# Sensors.net
KiCad netlist of a schematic drawn in Altium Designer
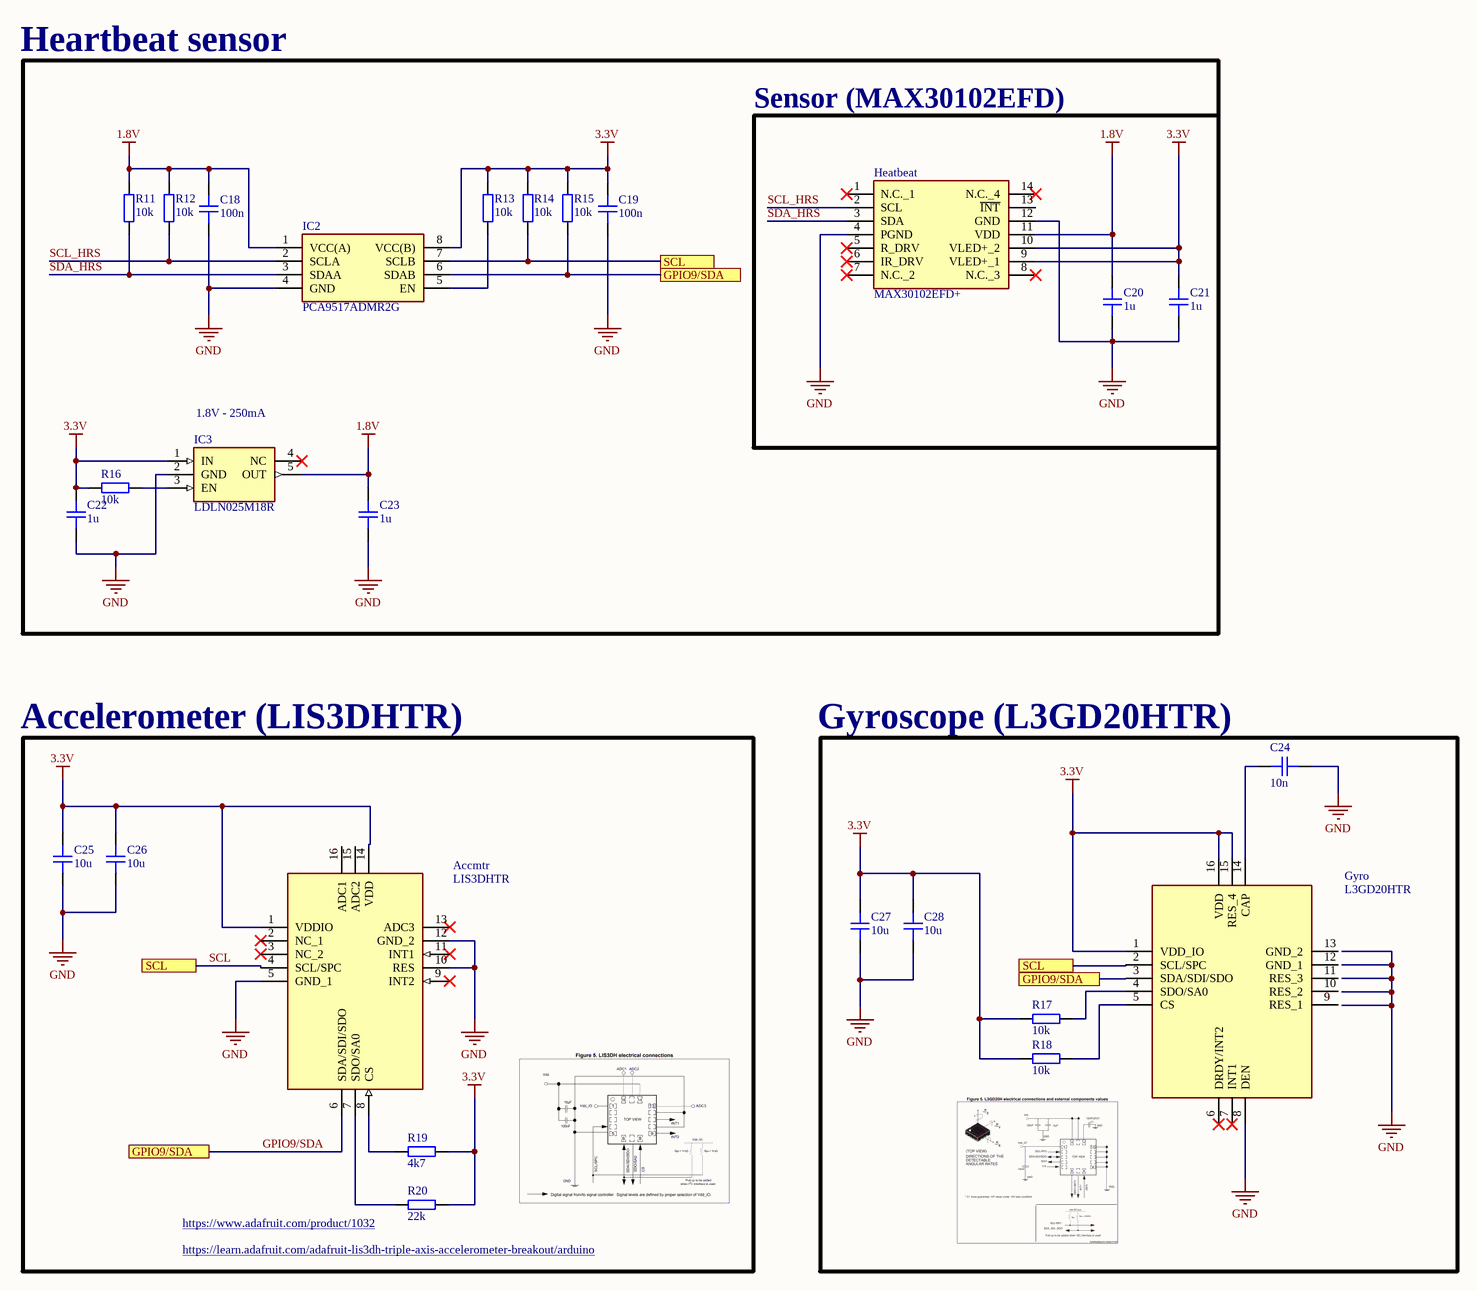
[diagram p0: Sensors.SchDoc]

(export (version "E")
  (design (tool "Eeschema 10.0.6"))
  (components
    (comp (ref "Accmtr")
      (value "LIS3DHTR")
      (footprint "PCB_Lib_DaanHeetkamp:LIS3DHTR")
      (description "Accelerometer")
      (fields (field (name "MOUSER PART NUMBER") "511-LIS3DHTR"))
      (libsource (lib "Schem_Lib_DaanHeetkamp.") (part "LIS3DHTR"))
    )
    (comp (ref "C18")
      (value "100n")
      (footprint "CAP_1206")
      (description "Capacitor SMD 1206 16V")
      (libsource (lib "Schem_Lib_DaanHeetkamp.") (part "CAP_1206_16V"))
    )
    (comp (ref "C19")
      (value "100n")
      (footprint "CAP_1206")
      (description "Capacitor SMD 1206 16V")
      (libsource (lib "Schem_Lib_DaanHeetkamp.") (part "CAP_1206_16V"))
    )
    (comp (ref "C20")
      (value "1u")
      (footprint "CAP_1206")
      (description "Capacitor SMD 1206 16V")
      (libsource (lib "Schem_Lib_DaanHeetkamp.") (part "CAP_1206_16V"))
    )
    (comp (ref "C21")
      (value "1u")
      (footprint "CAP_1206")
      (description "Capacitor SMD 1206 16V")
      (libsource (lib "Schem_Lib_DaanHeetkamp.") (part "CAP_1206_16V"))
    )
    (comp (ref "C22")
      (value "1u")
      (footprint "CAP_1206")
      (description "Capacitor SMD 1206 16V")
      (libsource (lib "Schem_Lib_DaanHeetkamp.") (part "CAP_1206_16V"))
    )
    (comp (ref "C23")
      (value "1u")
      (footprint "CAP_1206")
      (description "Capacitor SMD 1206 16V")
      (libsource (lib "Schem_Lib_DaanHeetkamp.") (part "CAP_1206_16V"))
    )
    (comp (ref "C24")
      (value "10n")
      (footprint "CAP_1206")
      (description "Capacitor SMD 1206 50V")
      (libsource (lib "Schem_Lib_DaanHeetkamp.") (part "CAP_1206_50V"))
    )
    (comp (ref "C25")
      (value "10u")
      (footprint "CAP_1206")
      (description "Capacitor SMD 1206 50V")
      (libsource (lib "Schem_Lib_DaanHeetkamp.") (part "CAP_1206_50V"))
    )
    (comp (ref "C26")
      (value "10u")
      (footprint "CAP_1206")
      (description "Capacitor SMD 1206 50V")
      (libsource (lib "Schem_Lib_DaanHeetkamp.") (part "CAP_1206_50V"))
    )
    (comp (ref "C27")
      (value "10u")
      (footprint "CAP_1206")
      (description "Capacitor SMD 1206 50V")
      (libsource (lib "Schem_Lib_DaanHeetkamp.") (part "CAP_1206_50V"))
    )
    (comp (ref "C28")
      (value "10u")
      (footprint "CAP_1206")
      (description "Capacitor SMD 1206 50V")
      (libsource (lib "Schem_Lib_DaanHeetkamp.") (part "CAP_1206_50V"))
    )
    (comp (ref "Gyro")
      (value "L3GD20HTR")
      (footprint "PCB_Lib_DaanHeetkamp:H3LIS100DLTR")
      (description "MEMS motion sensor:\r\n three-axis digital output gyroscope")
      (fields (field (name "MOUSER PART NUMBER") "511-L3GD20HTR"))
      (libsource (lib "Schem_Lib_DaanHeetkamp.") (part "L3GD20HTR"))
    )
    (comp (ref "Heatbeat")
      (value "MAX30102EFD+")
      (footprint "PCB_Lib_DaanHeetkamp:14-LEAD-OESIP")
      (description "Integrated Circuit")
      (fields (field (name "MOUSER PART NUMBER") "700-MAX30102EFD+"))
      (libsource (lib "Schem_Lib_DaanHeetkamp.") (part "MAX30102EFD+"))
    )
    (comp (ref "IC2")
      (value "PCA9517ADMR2G")
      (footprint "PCB_Lib_DaanHeetkamp:SOP65P490X110-8N")
      (description "Integrated Circuit")
      (fields (field (name "MOUSER PART NUMBER") "863-PCA9517ADMR2G"))
      (libsource (lib "Schem_Lib_DaanHeetkamp.") (part "PCA9517ADMR2G"))
    )
    (comp (ref "IC3")
      (value "LDLN025M18R")
      (footprint "PCB_Lib_DaanHeetkamp:SOT95P280X145-5N")
      (description "Integrated Circuit")
      (fields (field (name "MOUSER PART NUMBER") "511-LDLN025M18R"))
      (libsource (lib "Schem_Lib_DaanHeetkamp.") (part "LDLN025M18R"))
    )
    (comp (ref "R11")
      (value "10k")
      (footprint "RES_1206")
      (description "Resistor SMD 1206")
      (libsource (lib "Schem_Lib_DaanHeetkamp.") (part "RES_1206"))
    )
    (comp (ref "R12")
      (value "10k")
      (footprint "RES_1206")
      (description "Resistor SMD 1206")
      (libsource (lib "Schem_Lib_DaanHeetkamp.") (part "RES_1206"))
    )
    (comp (ref "R13")
      (value "10k")
      (footprint "RES_1206")
      (description "Resistor SMD 1206")
      (libsource (lib "Schem_Lib_DaanHeetkamp.") (part "RES_1206"))
    )
    (comp (ref "R14")
      (value "10k")
      (footprint "RES_1206")
      (description "Resistor SMD 1206")
      (libsource (lib "Schem_Lib_DaanHeetkamp.") (part "RES_1206"))
    )
    (comp (ref "R15")
      (value "10k")
      (footprint "RES_1206")
      (description "Resistor SMD 1206")
      (libsource (lib "Schem_Lib_DaanHeetkamp.") (part "RES_1206"))
    )
    (comp (ref "R16")
      (value "10k")
      (footprint "RES_1206")
      (description "Resistor SMD 1206")
      (libsource (lib "Schem_Lib_DaanHeetkamp.") (part "RES_1206"))
    )
    (comp (ref "R17")
      (value "10k")
      (footprint "RES_1206")
      (description "Resistor SMD 1206")
      (libsource (lib "Schem_Lib_DaanHeetkamp.") (part "RES_1206"))
    )
    (comp (ref "R18")
      (value "10k")
      (footprint "RES_1206")
      (description "Resistor SMD 1206")
      (libsource (lib "Schem_Lib_DaanHeetkamp.") (part "RES_1206"))
    )
    (comp (ref "R19")
      (value "4k7")
      (footprint "RES_1206")
      (description "Resistor SMD 1206")
      (libsource (lib "Schem_Lib_DaanHeetkamp.") (part "RES_1206"))
    )
    (comp (ref "R20")
      (value "22k")
      (footprint "RES_1206")
      (description "Resistor SMD 1206")
      (libsource (lib "Schem_Lib_DaanHeetkamp.") (part "RES_1206"))
    )
  )
  (nets
    (net (code "1") (name "/GPIO9{slash}SDA") (class "Default")
      (node (ref "Accmtr") (pin "6") (pinfunction "SDA/SDI/SDO_6") (pintype "passive"))
      (node (ref "Gyro") (pin "3") (pinfunction "SDA/SDI/SDO_3") (pintype "passive"))
      (node (ref "IC2") (pin "6") (pinfunction "SDAB_6") (pintype "passive"))
      (node (ref "R15") (pin "2") (pinfunction "2_2") (pintype "passive"))
    )
    (net (code "2") (name "/SCL") (class "Default")
      (node (ref "Accmtr") (pin "4") (pinfunction "SCL/SPC_4") (pintype "passive"))
      (node (ref "Gyro") (pin "2") (pinfunction "SCL/SPC_2") (pintype "passive"))
      (node (ref "IC2") (pin "7") (pinfunction "SCLB_7") (pintype "passive"))
      (node (ref "R14") (pin "2") (pinfunction "2_2") (pintype "passive"))
    )
    (net (code "3") (name "/SCL_HRS") (class "Default")
      (node (ref "Heatbeat") (pin "2") (pinfunction "SCL_2") (pintype "passive"))
      (node (ref "IC2") (pin "2") (pinfunction "SCLA_2") (pintype "passive"))
      (node (ref "R12") (pin "2") (pinfunction "2_2") (pintype "passive"))
    )
    (net (code "4") (name "/SDA_HRS") (class "Default")
      (node (ref "Heatbeat") (pin "3") (pinfunction "SDA_3") (pintype "passive"))
      (node (ref "IC2") (pin "3") (pinfunction "SDAA_3") (pintype "passive"))
      (node (ref "R11") (pin "2") (pinfunction "2_2") (pintype "passive"))
    )
    (net (code "5") (name "1.8V") (class "Default")
      (node (ref "C18") (pin "2") (pinfunction "2_2") (pintype "passive"))
      (node (ref "C20") (pin "2") (pinfunction "2_2") (pintype "passive"))
      (node (ref "C23") (pin "2") (pinfunction "2_2") (pintype "passive"))
      (node (ref "Heatbeat") (pin "11") (pinfunction "VDD_11") (pintype "passive"))
      (node (ref "IC2") (pin "1") (pinfunction "VCC(A)_1") (pintype "passive"))
      (node (ref "IC3") (pin "5") (pinfunction "OUT_5") (pintype "output"))
      (node (ref "R11") (pin "1") (pinfunction "1_1") (pintype "passive"))
      (node (ref "R12") (pin "1") (pinfunction "1_1") (pintype "passive"))
    )
    (net (code "6") (name "3.3V") (class "Default")
      (node (ref "Accmtr") (pin "1") (pinfunction "VDDIO_1") (pintype "power_in"))
      (node (ref "Accmtr") (pin "14") (pinfunction "VDD_14") (pintype "power_in"))
      (node (ref "C19") (pin "2") (pinfunction "2_2") (pintype "passive"))
      (node (ref "C21") (pin "2") (pinfunction "2_2") (pintype "passive"))
      (node (ref "C22") (pin "2") (pinfunction "2_2") (pintype "passive"))
      (node (ref "C25") (pin "2") (pinfunction "2_2") (pintype "passive"))
      (node (ref "C26") (pin "2") (pinfunction "2_2") (pintype "passive"))
      (node (ref "C27") (pin "2") (pinfunction "2_2") (pintype "passive"))
      (node (ref "C28") (pin "2") (pinfunction "2_2") (pintype "passive"))
      (node (ref "Gyro") (pin "1") (pinfunction "VDD_IO_1") (pintype "passive"))
      (node (ref "Gyro") (pin "15") (pinfunction "RES_4_15") (pintype "passive"))
      (node (ref "Gyro") (pin "16") (pinfunction "VDD_16") (pintype "passive"))
      (node (ref "Heatbeat") (pin "10") (pinfunction "VLED+_2_10") (pintype "passive"))
      (node (ref "Heatbeat") (pin "9") (pinfunction "VLED+_1_9") (pintype "passive"))
      (node (ref "IC2") (pin "8") (pinfunction "VCC(B)_8") (pintype "passive"))
      (node (ref "IC3") (pin "1") (pinfunction "IN_1") (pintype "input"))
      (node (ref "R13") (pin "1") (pinfunction "1_1") (pintype "passive"))
      (node (ref "R14") (pin "1") (pinfunction "1_1") (pintype "passive"))
      (node (ref "R15") (pin "1") (pinfunction "1_1") (pintype "passive"))
      (node (ref "R16") (pin "1") (pinfunction "1_1") (pintype "passive"))
      (node (ref "R17") (pin "2") (pinfunction "2_2") (pintype "passive"))
      (node (ref "R18") (pin "2") (pinfunction "2_2") (pintype "passive"))
      (node (ref "R19") (pin "1") (pinfunction "1_1") (pintype "passive"))
      (node (ref "R20") (pin "1") (pinfunction "1_1") (pintype "passive"))
    )
    (net (code "7") (name "GND") (class "Default")
      (node (ref "Accmtr") (pin "10") (pinfunction "RES_10") (pintype "passive"))
      (node (ref "Accmtr") (pin "12") (pinfunction "GND_2_12") (pintype "power_in"))
      (node (ref "Accmtr") (pin "5") (pinfunction "GND_1_5") (pintype "power_in"))
      (node (ref "C18") (pin "1") (pinfunction "1_1") (pintype "passive"))
      (node (ref "C19") (pin "1") (pinfunction "1_1") (pintype "passive"))
      (node (ref "C20") (pin "1") (pinfunction "1_1") (pintype "passive"))
      (node (ref "C21") (pin "1") (pinfunction "1_1") (pintype "passive"))
      (node (ref "C22") (pin "1") (pinfunction "1_1") (pintype "passive"))
      (node (ref "C23") (pin "1") (pinfunction "1_1") (pintype "passive"))
      (node (ref "C24") (pin "2") (pinfunction "2_2") (pintype "passive"))
      (node (ref "C25") (pin "1") (pinfunction "1_1") (pintype "passive"))
      (node (ref "C26") (pin "1") (pinfunction "1_1") (pintype "passive"))
      (node (ref "C27") (pin "1") (pinfunction "1_1") (pintype "passive"))
      (node (ref "C28") (pin "1") (pinfunction "1_1") (pintype "passive"))
      (node (ref "Gyro") (pin "8") (pinfunction "DEN_8") (pintype "passive"))
      (node (ref "Heatbeat") (pin "12") (pinfunction "GND_12") (pintype "passive"))
      (node (ref "Heatbeat") (pin "4") (pinfunction "PGND_4") (pintype "passive"))
      (node (ref "IC2") (pin "4") (pinfunction "GND_4") (pintype "passive"))
      (node (ref "IC3") (pin "2") (pinfunction "GND_2") (pintype "power_in"))
    )
    (net (code "8") (name "Net-(Accmtr-CS)") (class "Default")
      (node (ref "Accmtr") (pin "8") (pinfunction "CS_8") (pintype "input"))
      (node (ref "R19") (pin "2") (pinfunction "2_2") (pintype "passive"))
    )
    (net (code "9") (name "Net-(Accmtr-SDO{slash}SA0)") (class "Default")
      (node (ref "Accmtr") (pin "7") (pinfunction "SDO/SA0_7") (pintype "passive"))
      (node (ref "R20") (pin "2") (pinfunction "2_2") (pintype "passive"))
    )
    (net (code "10") (name "Net-(Gyro-CAP)") (class "Default")
      (node (ref "C24") (pin "1") (pinfunction "1_1") (pintype "passive"))
      (node (ref "Gyro") (pin "14") (pinfunction "CAP_14") (pintype "passive"))
    )
    (net (code "11") (name "Net-(Gyro-CS)") (class "Default")
      (node (ref "Gyro") (pin "5") (pinfunction "CS_5") (pintype "passive"))
      (node (ref "R18") (pin "1") (pinfunction "1_1") (pintype "passive"))
    )
    (net (code "12") (name "Net-(Gyro-SDO{slash}SA0)") (class "Default")
      (node (ref "Gyro") (pin "4") (pinfunction "SDO/SA0_4") (pintype "passive"))
      (node (ref "R17") (pin "1") (pinfunction "1_1") (pintype "passive"))
    )
    (net (code "13") (name "Net-(IC2-EN)") (class "Default")
      (node (ref "IC2") (pin "5") (pinfunction "EN_5") (pintype "passive"))
      (node (ref "R13") (pin "2") (pinfunction "2_2") (pintype "passive"))
    )
    (net (code "14") (name "Net-(IC3-EN)") (class "Default")
      (node (ref "IC3") (pin "3") (pinfunction "EN_3") (pintype "input"))
      (node (ref "R16") (pin "2") (pinfunction "2_2") (pintype "passive"))
    )
    (net (code "15") (name "unconnected-(Accmtr-ADC1-Pad16)") (class "Default")
      (node (ref "Accmtr") (pin "16") (pinfunction "ADC1_16") (pintype "passive"))
    )
    (net (code "16") (name "unconnected-(Accmtr-ADC2-Pad15)") (class "Default")
      (node (ref "Accmtr") (pin "15") (pinfunction "ADC2_15") (pintype "passive"))
    )
    (net (code "17") (name "unconnected-(Accmtr-ADC3-Pad13)") (class "Default")
      (node (ref "Accmtr") (pin "13") (pinfunction "ADC3_13") (pintype "passive+no_connect"))
    )
    (net (code "18") (name "unconnected-(Accmtr-INT1-Pad11)") (class "Default")
      (node (ref "Accmtr") (pin "11") (pinfunction "INT1_11") (pintype "input+no_connect"))
    )
    (net (code "19") (name "unconnected-(Accmtr-INT2-Pad9)") (class "Default")
      (node (ref "Accmtr") (pin "9") (pinfunction "INT2_9") (pintype "input+no_connect"))
    )
    (net (code "20") (name "unconnected-(Accmtr-NC_1-Pad2)") (class "Default")
      (node (ref "Accmtr") (pin "2") (pinfunction "NC_1_2") (pintype "passive+no_connect"))
    )
    (net (code "21") (name "unconnected-(Accmtr-NC_2-Pad3)") (class "Default")
      (node (ref "Accmtr") (pin "3") (pinfunction "NC_2_3") (pintype "passive+no_connect"))
    )
    (net (code "22") (name "unconnected-(Gyro-DRDY{slash}INT2-Pad6)") (class "Default")
      (node (ref "Gyro") (pin "6") (pinfunction "DRDY/INT2_6") (pintype "passive+no_connect"))
    )
    (net (code "23") (name "unconnected-(Gyro-GND_1-Pad12)") (class "Default")
      (node (ref "Gyro") (pin "12") (pinfunction "GND_1_12") (pintype "passive"))
    )
    (net (code "24") (name "unconnected-(Gyro-GND_2-Pad13)") (class "Default")
      (node (ref "Gyro") (pin "13") (pinfunction "GND_2_13") (pintype "passive"))
    )
    (net (code "25") (name "unconnected-(Gyro-INT1-Pad7)") (class "Default")
      (node (ref "Gyro") (pin "7") (pinfunction "INT1_7") (pintype "passive+no_connect"))
    )
    (net (code "26") (name "unconnected-(Gyro-RES_1-Pad9)") (class "Default")
      (node (ref "Gyro") (pin "9") (pinfunction "RES_1_9") (pintype "passive"))
    )
    (net (code "27") (name "unconnected-(Gyro-RES_2-Pad10)") (class "Default")
      (node (ref "Gyro") (pin "10") (pinfunction "RES_2_10") (pintype "passive"))
    )
    (net (code "28") (name "unconnected-(Gyro-RES_3-Pad11)") (class "Default")
      (node (ref "Gyro") (pin "11") (pinfunction "RES_3_11") (pintype "passive"))
    )
    (net (code "29") (name "unconnected-(Heatbeat-IR_DRV-Pad6)") (class "Default")
      (node (ref "Heatbeat") (pin "6") (pinfunction "IR_DRV_6") (pintype "passive+no_connect"))
    )
    (net (code "30") (name "unconnected-(Heatbeat-N.C._1-Pad1)") (class "Default")
      (node (ref "Heatbeat") (pin "1") (pinfunction "N.C._1_1") (pintype "passive+no_connect"))
    )
    (net (code "31") (name "unconnected-(Heatbeat-N.C._2-Pad7)") (class "Default")
      (node (ref "Heatbeat") (pin "7") (pinfunction "N.C._2_7") (pintype "passive+no_connect"))
    )
    (net (code "32") (name "unconnected-(Heatbeat-N.C._3-Pad8)") (class "Default")
      (node (ref "Heatbeat") (pin "8") (pinfunction "N.C._3_8") (pintype "passive+no_connect"))
    )
    (net (code "33") (name "unconnected-(Heatbeat-N.C._4-Pad14)") (class "Default")
      (node (ref "Heatbeat") (pin "14") (pinfunction "N.C._4_14") (pintype "passive+no_connect"))
    )
    (net (code "34") (name "unconnected-(Heatbeat-R_DRV-Pad5)") (class "Default")
      (node (ref "Heatbeat") (pin "5") (pinfunction "R_DRV_5") (pintype "passive+no_connect"))
    )
    (net (code "35") (name "unconnected-(Heatbeat-~{INT}-Pad13)") (class "Default")
      (node (ref "Heatbeat") (pin "13") (pinfunction "~{INT}_13") (pintype "passive"))
    )
    (net (code "36") (name "unconnected-(IC3-NC-Pad4)") (class "Default")
      (node (ref "IC3") (pin "4") (pinfunction "NC_4") (pintype "passive+no_connect"))
    )
  )
)
